# blinky.net
KiCad netlist of a schematic drawn in EAGLE
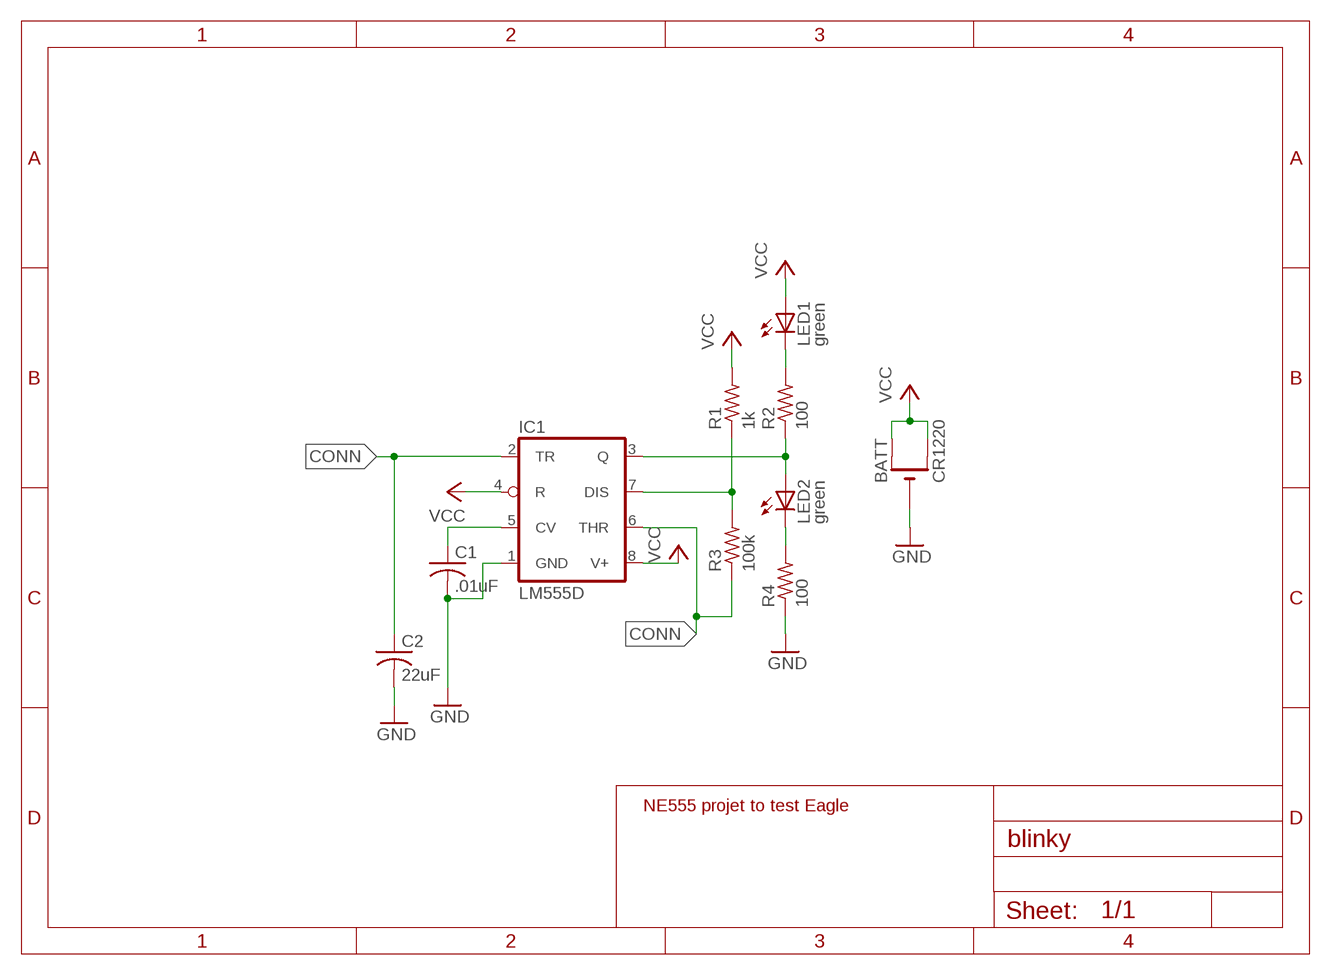
[diagram p0: schematic, sheet 1]

(export (version "E")
  (design (tool "Eeschema 10.0.6"))
  (components
    (comp (ref "BATT")
      (value "CR1220")
      (footprint "eagle-import:CR1220-SMD")
      (libsource (lib "eagle-import") (part "CR1220SMT"))
    )
    (comp (ref "C1")
      (value ".01uF")
      (footprint "eagle-import:C0805")
      (libsource (lib "eagle-import") (part "C-USC0805"))
    )
    (comp (ref "C2")
      (value "22uF")
      (footprint "eagle-import:C0805")
      (libsource (lib "eagle-import") (part "C-USC0805"))
    )
    (comp (ref "IC1")
      (value "LM555D")
      (footprint "eagle-import:SO08")
      (libsource (lib "eagle-import") (part "555DLM"))
    )
    (comp (ref "LED1")
      (value "green")
      (footprint "eagle-import:CHIPLED_0805")
      (libsource (lib "eagle-import") (part "LEDCHIPLED_0805"))
    )
    (comp (ref "LED2")
      (value "green")
      (footprint "eagle-import:CHIPLED_0805")
      (libsource (lib "eagle-import") (part "LEDCHIPLED_0805"))
    )
    (comp (ref "R1")
      (value "1k")
      (footprint "eagle-import:R0805")
      (libsource (lib "eagle-import") (part "R-US_R0805"))
    )
    (comp (ref "R2")
      (value "100")
      (footprint "eagle-import:R0805")
      (libsource (lib "eagle-import") (part "R-US_R0805"))
    )
    (comp (ref "R3")
      (value "100k")
      (footprint "eagle-import:R0805")
      (libsource (lib "eagle-import") (part "R-US_R0805"))
    )
    (comp (ref "R4")
      (value "100")
      (footprint "eagle-import:R0805")
      (libsource (lib "eagle-import") (part "R-US_R0805"))
    )
  )
  (nets
    (net (code "1") (name "CONN") (class "Default")
      (node (ref "C2") (pin "1") (pinfunction "1_1") (pintype "passive"))
      (node (ref "IC1") (pin "2") (pinfunction "TR_2") (pintype "input"))
      (node (ref "IC1") (pin "6") (pinfunction "THR_6") (pintype "input"))
      (node (ref "R3") (pin "1") (pinfunction "1_1") (pintype "passive"))
    )
    (net (code "2") (name "GND") (class "Default")
      (node (ref "BATT") (pin "-") (pinfunction "-_-") (pintype "passive"))
      (node (ref "C1") (pin "2") (pinfunction "2_2") (pintype "passive"))
      (node (ref "C2") (pin "2") (pinfunction "2_2") (pintype "passive"))
      (node (ref "IC1") (pin "1") (pinfunction "GND_1") (pintype "power_in"))
      (node (ref "R4") (pin "1") (pinfunction "1_1") (pintype "passive"))
    )
    (net (code "3") (name "Net-(IC1-CV)") (class "Default")
      (node (ref "C1") (pin "1") (pinfunction "1_1") (pintype "passive"))
      (node (ref "IC1") (pin "5") (pinfunction "CV_5") (pintype "input"))
    )
    (net (code "4") (name "Net-(IC1-DIS)") (class "Default")
      (node (ref "IC1") (pin "7") (pinfunction "DIS_7") (pintype "input"))
      (node (ref "R1") (pin "1") (pinfunction "1_1") (pintype "passive"))
      (node (ref "R3") (pin "2") (pinfunction "2_2") (pintype "passive"))
    )
    (net (code "5") (name "Net-(IC1-Q)") (class "Default")
      (node (ref "IC1") (pin "3") (pinfunction "Q_3") (pintype "output"))
      (node (ref "LED2") (pin "A") (pinfunction "A_A") (pintype "passive"))
      (node (ref "R2") (pin "1") (pinfunction "1_1") (pintype "passive"))
    )
    (net (code "6") (name "Net-(LED1-PadC)") (class "Default")
      (node (ref "LED1") (pin "C") (pinfunction "C_C") (pintype "passive"))
      (node (ref "R2") (pin "2") (pinfunction "2_2") (pintype "passive"))
    )
    (net (code "7") (name "Net-(LED2-PadC)") (class "Default")
      (node (ref "LED2") (pin "C") (pinfunction "C_C") (pintype "passive"))
      (node (ref "R4") (pin "2") (pinfunction "2_2") (pintype "passive"))
    )
    (net (code "8") (name "VCC") (class "Default")
      (node (ref "BATT") (pin "+$1") (pinfunction "+_+$1") (pintype "passive"))
      (node (ref "BATT") (pin "+$2") (pinfunction "+1_+$2") (pintype "passive"))
      (node (ref "IC1") (pin "4") (pinfunction "R_4") (pintype "input"))
      (node (ref "IC1") (pin "8") (pinfunction "V+_8") (pintype "power_in"))
      (node (ref "LED1") (pin "A") (pinfunction "A_A") (pintype "passive"))
      (node (ref "R1") (pin "2") (pinfunction "2_2") (pintype "passive"))
    )
  )
)
